# 4_cpu.net
KiCad netlist of a schematic drawn in Altium Designer
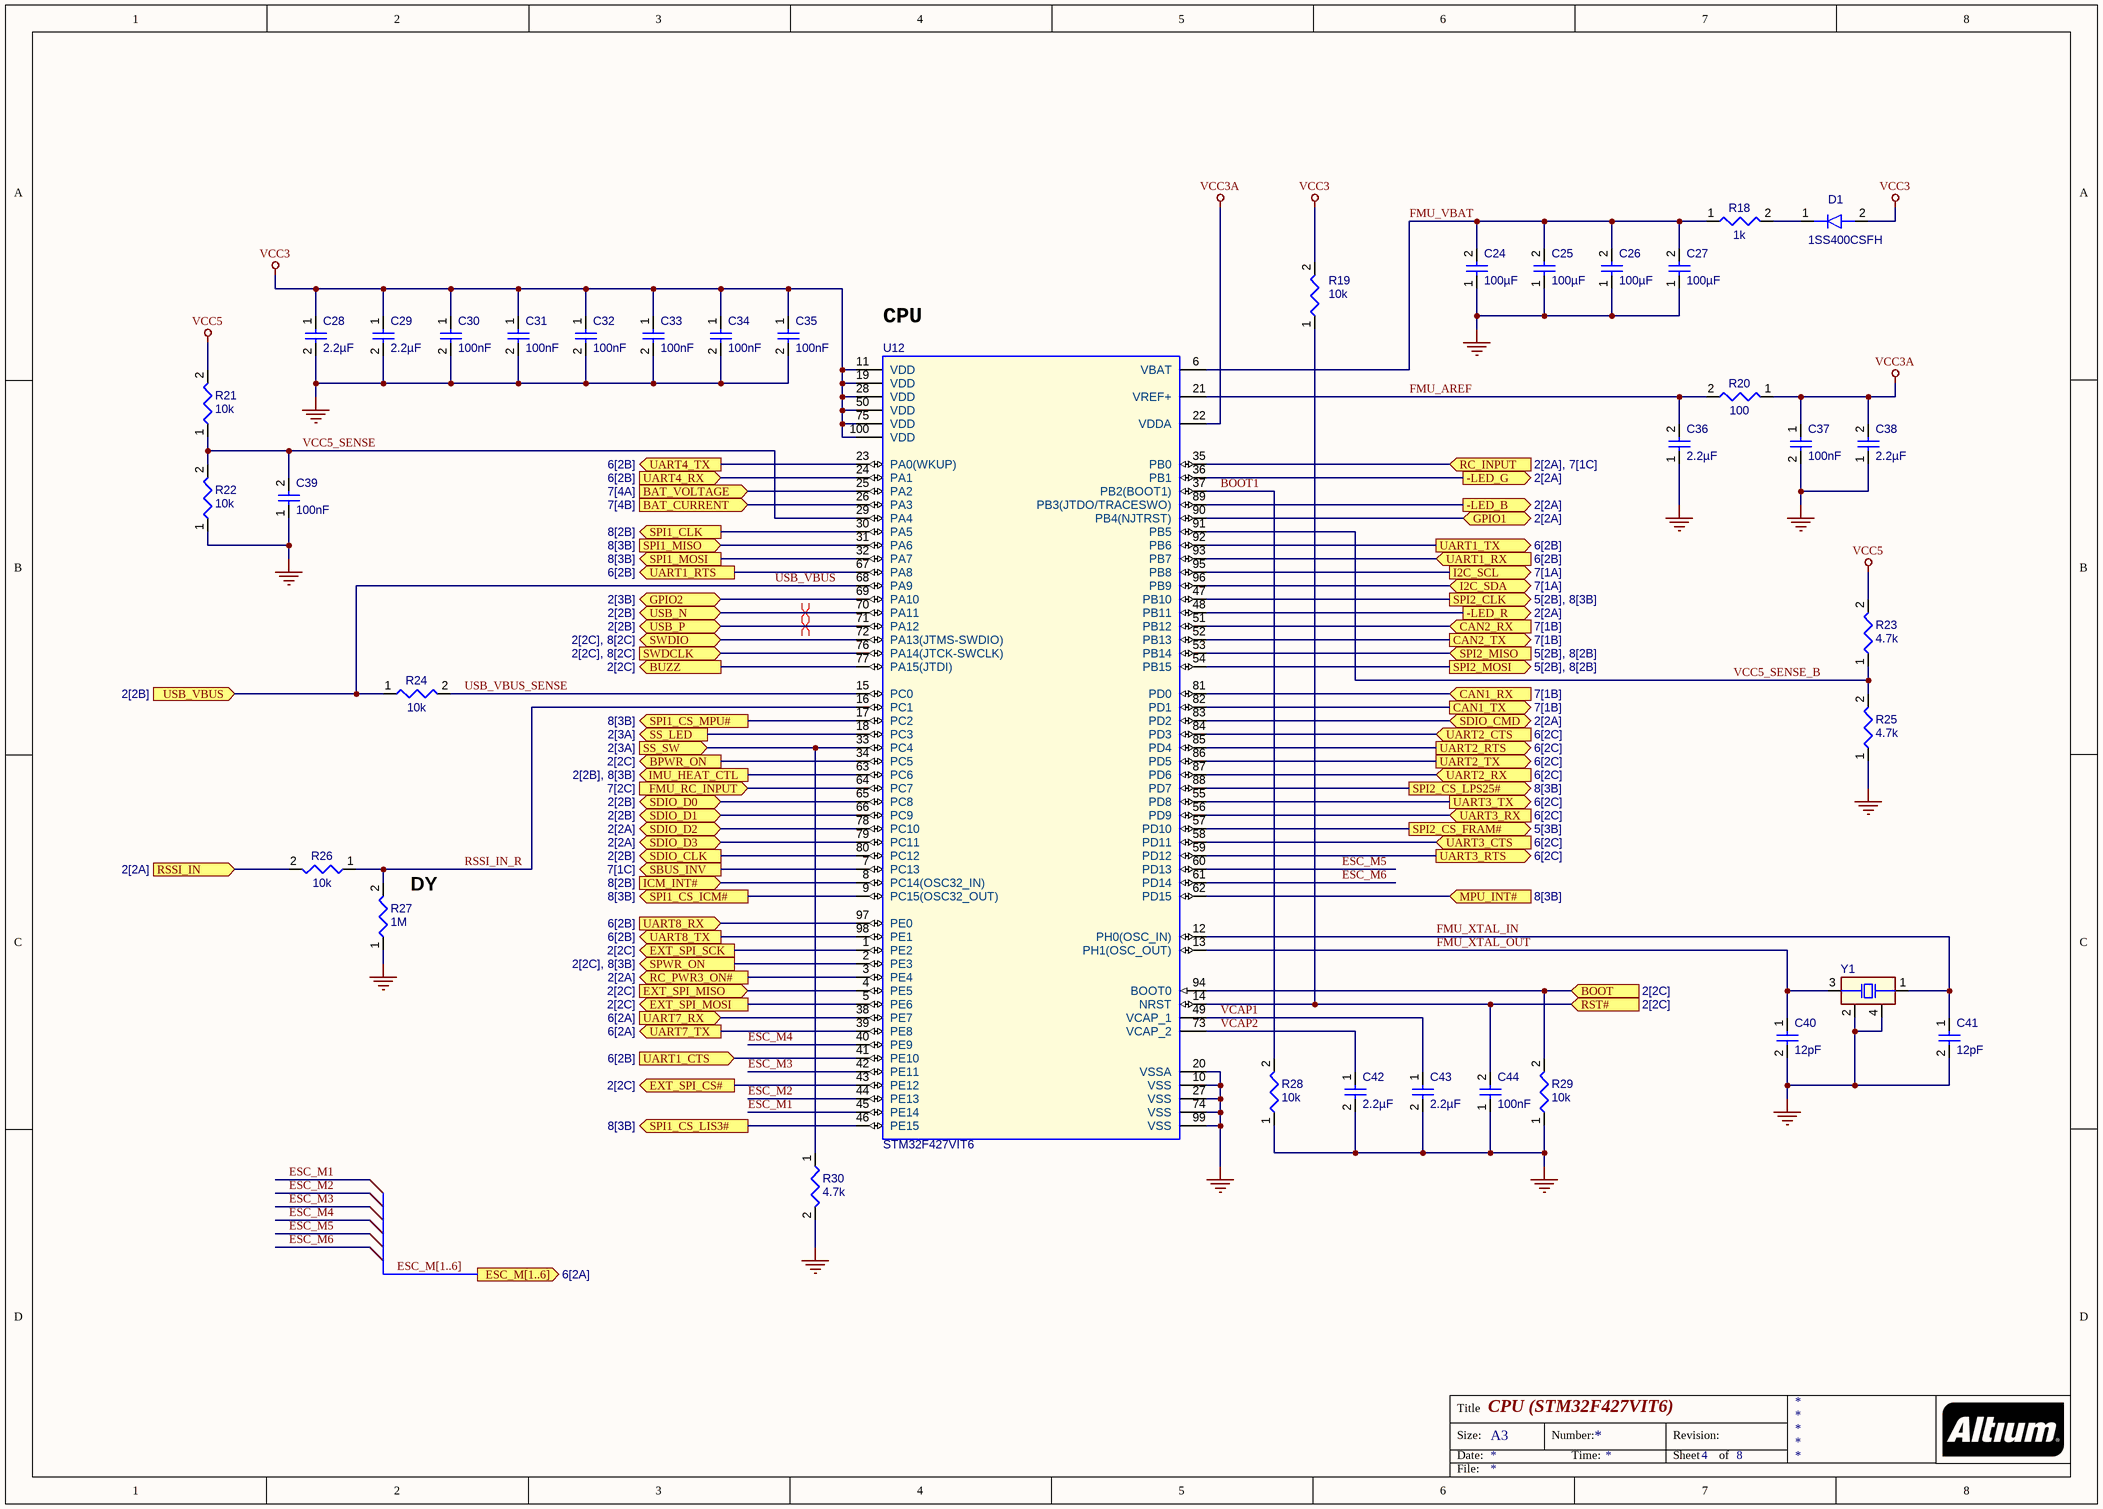
[diagram p0: 4_cpu.SchDoc]

(export (version "E")
  (design (tool "Eeschema 10.0.6"))
  (components
    (comp (ref "C24")
      (value "100µF")
      (footprint "CAPC0805(2012)145_L")
      (description "Chip Capacitor, 100µF +/-20%, 6.3V, 0805, Thickness 1.45 mm")
      (fields (field (name "TOLERANCE") "10%") (field (name "Comment") "Capacitor 100µF +/-20% 6.3V 0805"))
      (libsource (lib "<Company> Server") (part "CAP-NP-2"))
    )
    (comp (ref "C25")
      (value "100µF")
      (footprint "CAPC0805(2012)145_L")
      (description "Chip Capacitor, 100µF +/-20%, 6.3V, 0805, Thickness 1.45 mm")
      (fields (field (name "TOLERANCE") "10%") (field (name "Comment") "Capacitor 100µF +/-20% 6.3V 0805"))
      (libsource (lib "<Company> Server") (part "CAP-NP-2"))
    )
    (comp (ref "C26")
      (value "100µF")
      (footprint "CAPC0805(2012)145_L")
      (description "Chip Capacitor, 100µF +/-20%, 6.3V, 0805, Thickness 1.45 mm")
      (fields (field (name "TOLERANCE") "10%") (field (name "Comment") "Capacitor 100µF +/-20% 6.3V 0805"))
      (libsource (lib "<Company> Server") (part "CAP-NP-2"))
    )
    (comp (ref "C27")
      (value "100µF")
      (footprint "CAPC0805(2012)145_L")
      (description "Chip Capacitor, 100µF +/-20%, 6.3V, 0805, Thickness 1.45 mm")
      (fields (field (name "TOLERANCE") "10%") (field (name "Comment") "Capacitor 100µF +/-20% 6.3V 0805"))
      (libsource (lib "<Company> Server") (part "CAP-NP-2"))
    )
    (comp (ref "C28")
      (value "2.2µF")
      (footprint "CAPC0402(1005)60_L")
      (description "Chip Capacitor, 2,2µF +/-20%, 10V, 0402, Thickness 0.6 mm")
      (fields (field (name "TOLERANCE") "10%") (field (name "Comment") "Capacitor 2,2µF +/-20% 10V 0402"))
      (libsource (lib "<Company> Server") (part "CAP-NP-2"))
    )
    (comp (ref "C29")
      (value "2.2µF")
      (footprint "CAPC0402(1005)60_L")
      (description "Chip Capacitor, 2,2µF +/-20%, 10V, 0402, Thickness 0.6 mm")
      (fields (field (name "TOLERANCE") "10%") (field (name "Comment") "Capacitor 2,2µF +/-20% 10V 0402"))
      (libsource (lib "<Company> Server") (part "CAP-NP-2"))
    )
    (comp (ref "C30")
      (value "100nF")
      (footprint "CAPC0402(1005)60_L")
      (description "Chip Capacitor, 100nF +/-20%, 10V, 0402, Thickness 0.6 mm")
      (fields (field (name "TOLERANCE") "20%") (field (name "Comment") "Capacitor 100nF +/-20% 10V 0402"))
      (libsource (lib "<Company> Server") (part "CAP-NP-2"))
    )
    (comp (ref "C31")
      (value "100nF")
      (footprint "CAPC0402(1005)60_L")
      (description "Chip Capacitor, 100nF +/-20%, 10V, 0402, Thickness 0.6 mm")
      (fields (field (name "TOLERANCE") "20%") (field (name "Comment") "Capacitor 100nF +/-20% 10V 0402"))
      (libsource (lib "<Company> Server") (part "CAP-NP-2"))
    )
    (comp (ref "C32")
      (value "100nF")
      (footprint "CAPC0402(1005)60_L")
      (description "Chip Capacitor, 100nF +/-20%, 10V, 0402, Thickness 0.6 mm")
      (fields (field (name "TOLERANCE") "20%") (field (name "Comment") "Capacitor 100nF +/-20% 10V 0402"))
      (libsource (lib "<Company> Server") (part "CAP-NP-2"))
    )
    (comp (ref "C33")
      (value "100nF")
      (footprint "CAPC0402(1005)60_L")
      (description "Chip Capacitor, 100nF +/-20%, 10V, 0402, Thickness 0.6 mm")
      (fields (field (name "TOLERANCE") "20%") (field (name "Comment") "Capacitor 100nF +/-20% 10V 0402"))
      (libsource (lib "<Company> Server") (part "CAP-NP-2"))
    )
    (comp (ref "C34")
      (value "100nF")
      (footprint "CAPC0402(1005)60_L")
      (description "Chip Capacitor, 100nF +/-20%, 10V, 0402, Thickness 0.6 mm")
      (fields (field (name "TOLERANCE") "20%") (field (name "Comment") "Capacitor 100nF +/-20% 10V 0402"))
      (libsource (lib "<Company> Server") (part "CAP-NP-2"))
    )
    (comp (ref "C35")
      (value "100nF")
      (footprint "CAPC0402(1005)60_L")
      (description "Chip Capacitor, 100nF +/-20%, 10V, 0402, Thickness 0.6 mm")
      (fields (field (name "TOLERANCE") "20%") (field (name "Comment") "Capacitor 100nF +/-20% 10V 0402"))
      (libsource (lib "<Company> Server") (part "CAP-NP-2"))
    )
    (comp (ref "C36")
      (value "2.2µF")
      (footprint "CAPC0402(1005)60_L")
      (description "Chip Capacitor, 2,2µF +/-20%, 10V, 0402, Thickness 0.6 mm")
      (fields (field (name "TOLERANCE") "10%") (field (name "Comment") "Capacitor 2,2µF +/-20% 10V 0402"))
      (libsource (lib "<Company> Server") (part "CAP-NP-2"))
    )
    (comp (ref "C37")
      (value "100nF")
      (footprint "CAPC0402(1005)60_L")
      (description "Chip Capacitor, 100nF +/-20%, 10V, 0402, Thickness 0.6 mm")
      (fields (field (name "TOLERANCE") "20%") (field (name "Comment") "Capacitor 100nF +/-20% 10V 0402"))
      (libsource (lib "<Company> Server") (part "CAP-NP-2"))
    )
    (comp (ref "C38")
      (value "2.2µF")
      (footprint "CAPC0402(1005)60_L")
      (description "Chip Capacitor, 2,2µF +/-20%, 10V, 0402, Thickness 0.6 mm")
      (fields (field (name "TOLERANCE") "10%") (field (name "Comment") "Capacitor 2,2µF +/-20% 10V 0402"))
      (libsource (lib "<Company> Server") (part "CAP-NP-2"))
    )
    (comp (ref "C39")
      (value "100nF")
      (footprint "CAPC0402(1005)60_L")
      (description "Chip Capacitor, 100nF +/-20%, 10V, 0402, Thickness 0.6 mm")
      (fields (field (name "TOLERANCE") "20%") (field (name "Comment") "Capacitor 100nF +/-20% 10V 0402"))
      (libsource (lib "<Company> Server") (part "CAP-NP-2"))
    )
    (comp (ref "C40")
      (value "12pF")
      (footprint "CAPC0402(1005)33_L")
      (description "Chip Capacitor, 12pF +/-10%, 50V, 0402, Thickness 0.33 mm")
      (fields (field (name "TOLERANCE") "20%") (field (name "Comment") "Capacitor 12pF +/-10% 50V 0402"))
      (libsource (lib "<Company> Server") (part "CAP-NP-2"))
    )
    (comp (ref "C41")
      (value "12pF")
      (footprint "CAPC0402(1005)33_L")
      (description "Chip Capacitor, 12pF +/-10%, 50V, 0402, Thickness 0.33 mm")
      (fields (field (name "TOLERANCE") "20%") (field (name "Comment") "Capacitor 12pF +/-10% 50V 0402"))
      (libsource (lib "<Company> Server") (part "CAP-NP-2"))
    )
    (comp (ref "C42")
      (value "2.2µF")
      (footprint "CAPC0402(1005)60_L")
      (description "Chip Capacitor, 2,2µF +/-20%, 10V, 0402, Thickness 0.6 mm")
      (fields (field (name "TOLERANCE") "10%") (field (name "Comment") "Capacitor 2,2µF +/-20% 10V 0402"))
      (libsource (lib "<Company> Server") (part "CAP-NP-2"))
    )
    (comp (ref "C43")
      (value "2.2µF")
      (footprint "CAPC0402(1005)60_L")
      (description "Chip Capacitor, 2,2µF +/-20%, 10V, 0402, Thickness 0.6 mm")
      (fields (field (name "TOLERANCE") "10%") (field (name "Comment") "Capacitor 2,2µF +/-20% 10V 0402"))
      (libsource (lib "<Company> Server") (part "CAP-NP-2"))
    )
    (comp (ref "C44")
      (value "100nF")
      (footprint "CAPC0402(1005)60_L")
      (description "Chip Capacitor, 100nF +/-20%, 10V, 0402, Thickness 0.6 mm")
      (fields (field (name "TOLERANCE") "20%") (field (name "Comment") "Capacitor 100nF +/-20% 10V 0402"))
      (libsource (lib "<Company> Server") (part "CAP-NP-2"))
    )
    (comp (ref "D1")
      (value "1SS400CSFH")
      (footprint "ROHM-VMN2-2_V")
      (description "Switching Diode (High Speed Switching), 80 V, 100 mA, 2-Pin SOD-923, RoHS, Tape and Reel")
      (libsource (lib "<Company> Server") (part "D-KA-2"))
    )
    (comp (ref "R18")
      (value "1k")
      (footprint "RESC0402(1005)_L")
      (description "Chip Resistor, 1 kOhms, +/-5 %, 63 mW, -55 to 155 degC, 0402")
      (fields (field (name "TOLERANCE") "5%") (field (name "POWER") "63mW"))
      (libsource (lib "<Company> Server") (part "RES-2"))
    )
    (comp (ref "R19")
      (value "10k")
      (footprint "RESC0402(1005)_L")
      (description "Chip Resistor, 10 kOhms, +/-1 %, 63 mW, -55 to 125 degC, 0402")
      (fields (field (name "TOLERANCE") "1%") (field (name "POWER") "63mW"))
      (libsource (lib "<Company> Server") (part "RES-2"))
    )
    (comp (ref "R20")
      (value "100")
      (footprint "RESC0402(1005)_L")
      (description "Chip Resistor, 100 Ohms, +/-1 %, 63 mW, -55 to 155 degC, 0402")
      (fields (field (name "TOLERANCE") "1%") (field (name "POWER") "63mW"))
      (libsource (lib "<Company> Server") (part "RES-2"))
    )
    (comp (ref "R21")
      (value "10k")
      (footprint "RESC0402(1005)_L")
      (description "Chip Resistor, 10 kOhms, +/-1 %, 63 mW, -55 to 125 degC, 0402")
      (fields (field (name "TOLERANCE") "1%") (field (name "POWER") "63mW"))
      (libsource (lib "<Company> Server") (part "RES-2"))
    )
    (comp (ref "R22")
      (value "10k")
      (footprint "RESC0402(1005)_L")
      (description "Chip Resistor, 10 kOhms, +/-1 %, 63 mW, -55 to 125 degC, 0402")
      (fields (field (name "TOLERANCE") "1%") (field (name "POWER") "63mW"))
      (libsource (lib "<Company> Server") (part "RES-2"))
    )
    (comp (ref "R23")
      (value "4.7k")
      (footprint "RESC0402(1005)_L")
      (description "Chip Resistor, 4,7 kOhms, +/-1 %, 63 mW, -55 to 155 degC, 0402")
      (fields (field (name "TOLERANCE") "1%") (field (name "POWER") "63mW"))
      (libsource (lib "<Company> Server") (part "RES-2"))
    )
    (comp (ref "R24")
      (value "10k")
      (footprint "RESC0402(1005)_L")
      (description "Chip Resistor, 10 kOhms, +/-1 %, 63 mW, -55 to 125 degC, 0402")
      (fields (field (name "TOLERANCE") "1%") (field (name "POWER") "63mW"))
      (libsource (lib "<Company> Server") (part "RES-2"))
    )
    (comp (ref "R25")
      (value "4.7k")
      (footprint "RESC0402(1005)_L")
      (description "Chip Resistor, 4,7 kOhms, +/-1 %, 63 mW, -55 to 155 degC, 0402")
      (fields (field (name "TOLERANCE") "1%") (field (name "POWER") "63mW"))
      (libsource (lib "<Company> Server") (part "RES-2"))
    )
    (comp (ref "R26")
      (value "10k")
      (footprint "RESC0402(1005)_L")
      (description "Chip Resistor, 10 kOhms, +/-1 %, 63 mW, -55 to 125 degC, 0402")
      (fields (field (name "TOLERANCE") "1%") (field (name "POWER") "63mW"))
      (libsource (lib "<Company> Server") (part "RES-2"))
    )
    (comp (ref "R27")
      (value "1M")
      (footprint "RESC0402(1005)_L")
      (description "Chip Resistor, 1 MOhms, +/-5 %, 63 mW, -55 to 155 degC, 0402")
      (fields (field (name "TOLERANCE") "5%") (field (name "POWER") "63mW"))
      (libsource (lib "<Company> Server") (part "RES-2"))
    )
    (comp (ref "R28")
      (value "10k")
      (footprint "RESC0402(1005)_L")
      (description "Chip Resistor, 10 kOhms, +/-1 %, 63 mW, -55 to 125 degC, 0402")
      (fields (field (name "TOLERANCE") "1%") (field (name "POWER") "63mW"))
      (libsource (lib "<Company> Server") (part "RES-2"))
    )
    (comp (ref "R29")
      (value "10k")
      (footprint "RESC0402(1005)_L")
      (description "Chip Resistor, 10 kOhms, +/-1 %, 63 mW, -55 to 125 degC, 0402")
      (fields (field (name "TOLERANCE") "1%") (field (name "POWER") "63mW"))
      (libsource (lib "<Company> Server") (part "RES-2"))
    )
    (comp (ref "R30")
      (value "4.7k")
      (footprint "RESC0402(1005)_L")
      (description "Chip Resistor, 4,7 kOhms, +/-1 %, 63 mW, -55 to 155 degC, 0402")
      (fields (field (name "TOLERANCE") "1%") (field (name "POWER") "63mW"))
      (libsource (lib "<Company> Server") (part "RES-2"))
    )
    (comp (ref "U12")
      (value "STM32F427VIT6")
      (footprint "STM-LQFP100")
      (libsource (lib "<Company> Server") (part "CMP-00125-5"))
    )
    (comp (ref "Y1")
      (value "FA-12824.0000MF10Z-W3")
      (footprint "EPSON-FA-128_V")
      (description "Crystal, 24 MHz, +/- 10 ppm, -20 to 75 degC, 4-Pin SMD, RoHS, Tape and Reel")
      (libsource (lib "<Company> Server") (part "CMP-00014-7"))
    )
  )
  (nets
    (net (code "1") (name "/-LED_B") (class "Default")
      (node (ref "U12") (pin "89") (pinfunction "PB3(JTDO/TRACESWO)_89") (pintype "bidirectional"))
    )
    (net (code "2") (name "/-LED_G") (class "Default")
      (node (ref "U12") (pin "36") (pinfunction "PB1_36") (pintype "bidirectional"))
    )
    (net (code "3") (name "/-LED_R") (class "Default")
      (node (ref "U12") (pin "48") (pinfunction "PB11_48") (pintype "bidirectional"))
    )
    (net (code "4") (name "/BAT_CURRENT") (class "Default")
      (node (ref "U12") (pin "26") (pinfunction "PA3_26") (pintype "bidirectional"))
    )
    (net (code "5") (name "/BAT_VOLTAGE") (class "Default")
      (node (ref "U12") (pin "25") (pinfunction "PA2_25") (pintype "bidirectional"))
    )
    (net (code "6") (name "/BOOT") (class "Default")
      (node (ref "R29") (pin "2") (pinfunction "2_2") (pintype "passive"))
      (node (ref "U12") (pin "94") (pinfunction "BOOT0_94") (pintype "input"))
    )
    (net (code "7") (name "/BOOT1") (class "Default")
      (node (ref "R28") (pin "2") (pinfunction "2_2") (pintype "passive"))
      (node (ref "U12") (pin "37") (pinfunction "PB2(BOOT1)_37") (pintype "bidirectional"))
    )
    (net (code "8") (name "/BPWR_ON") (class "Default")
      (node (ref "U12") (pin "34") (pinfunction "PC5_34") (pintype "bidirectional"))
    )
    (net (code "9") (name "/BUZZ") (class "Default")
      (node (ref "U12") (pin "77") (pinfunction "PA15(JTDI)_77") (pintype "bidirectional"))
    )
    (net (code "10") (name "/CAN1_RX") (class "Default")
      (node (ref "U12") (pin "81") (pinfunction "PD0_81") (pintype "bidirectional"))
    )
    (net (code "11") (name "/CAN1_TX") (class "Default")
      (node (ref "U12") (pin "82") (pinfunction "PD1_82") (pintype "bidirectional"))
    )
    (net (code "12") (name "/CAN2_RX") (class "Default")
      (node (ref "U12") (pin "51") (pinfunction "PB12_51") (pintype "bidirectional"))
    )
    (net (code "13") (name "/CAN2_TX") (class "Default")
      (node (ref "U12") (pin "52") (pinfunction "PB13_52") (pintype "bidirectional"))
    )
    (net (code "14") (name "/ESC_M1") (class "Default")
      (node (ref "U12") (pin "45") (pinfunction "PE14_45") (pintype "bidirectional"))
    )
    (net (code "15") (name "/ESC_M2") (class "Default")
      (node (ref "U12") (pin "44") (pinfunction "PE13_44") (pintype "bidirectional"))
    )
    (net (code "16") (name "/ESC_M3") (class "Default")
      (node (ref "U12") (pin "42") (pinfunction "PE11_42") (pintype "bidirectional"))
    )
    (net (code "17") (name "/ESC_M4") (class "Default")
      (node (ref "U12") (pin "40") (pinfunction "PE9_40") (pintype "bidirectional"))
    )
    (net (code "18") (name "/ESC_M5") (class "Default")
      (node (ref "U12") (pin "60") (pinfunction "PD13_60") (pintype "bidirectional"))
    )
    (net (code "19") (name "/ESC_M6") (class "Default")
      (node (ref "U12") (pin "61") (pinfunction "PD14_61") (pintype "bidirectional"))
    )
    (net (code "21") (name "/EXT_SPI_CS#") (class "Default")
      (node (ref "U12") (pin "43") (pinfunction "PE12_43") (pintype "bidirectional"))
    )
    (net (code "22") (name "/EXT_SPI_MISO") (class "Default")
      (node (ref "U12") (pin "4") (pinfunction "PE5_4") (pintype "bidirectional"))
    )
    (net (code "23") (name "/EXT_SPI_MOSI") (class "Default")
      (node (ref "U12") (pin "5") (pinfunction "PE6_5") (pintype "bidirectional"))
    )
    (net (code "24") (name "/EXT_SPI_SCK") (class "Default")
      (node (ref "U12") (pin "1") (pinfunction "PE2_1") (pintype "bidirectional"))
    )
    (net (code "25") (name "/FMU_AREF") (class "Default")
      (node (ref "C36") (pin "2") (pinfunction "2_2") (pintype "passive"))
      (node (ref "R20") (pin "2") (pinfunction "2_2") (pintype "passive"))
      (node (ref "U12") (pin "21") (pinfunction "VREF+_21") (pintype "power_in"))
    )
    (net (code "26") (name "/FMU_RC_INPUT") (class "Default")
      (node (ref "U12") (pin "64") (pinfunction "PC7_64") (pintype "bidirectional"))
    )
    (net (code "27") (name "/FMU_VBAT") (class "Default")
      (node (ref "C24") (pin "2") (pinfunction "2_2") (pintype "passive"))
      (node (ref "C25") (pin "2") (pinfunction "2_2") (pintype "passive"))
      (node (ref "C26") (pin "2") (pinfunction "2_2") (pintype "passive"))
      (node (ref "C27") (pin "2") (pinfunction "2_2") (pintype "passive"))
      (node (ref "R18") (pin "1") (pinfunction "1_1") (pintype "passive"))
      (node (ref "U12") (pin "6") (pinfunction "VBAT_6") (pintype "power_in"))
    )
    (net (code "28") (name "/FMU_XTAL_IN") (class "Default")
      (node (ref "C41") (pin "1") (pinfunction "1_1") (pintype "passive"))
      (node (ref "U12") (pin "12") (pinfunction "PH0(OSC_IN)_12") (pintype "bidirectional"))
      (node (ref "Y1") (pin "1") (pinfunction "X1_1") (pintype "passive"))
    )
    (net (code "29") (name "/FMU_XTAL_OUT") (class "Default")
      (node (ref "C40") (pin "1") (pinfunction "1_1") (pintype "passive"))
      (node (ref "U12") (pin "13") (pinfunction "PH1(OSC_OUT)_13") (pintype "bidirectional"))
      (node (ref "Y1") (pin "3") (pinfunction "X2_3") (pintype "passive"))
    )
    (net (code "30") (name "/GPIO1") (class "Default")
      (node (ref "U12") (pin "90") (pinfunction "PB4(NJTRST)_90") (pintype "bidirectional"))
    )
    (net (code "31") (name "/GPIO2") (class "Default")
      (node (ref "U12") (pin "69") (pinfunction "PA10_69") (pintype "bidirectional"))
    )
    (net (code "32") (name "/I2C_SCL") (class "Default")
      (node (ref "U12") (pin "95") (pinfunction "PB8_95") (pintype "bidirectional"))
    )
    (net (code "33") (name "/I2C_SDA") (class "Default")
      (node (ref "U12") (pin "96") (pinfunction "PB9_96") (pintype "bidirectional"))
    )
    (net (code "34") (name "/ICM_INT#") (class "Default")
      (node (ref "U12") (pin "8") (pinfunction "PC14(OSC32_IN)_8") (pintype "bidirectional"))
    )
    (net (code "35") (name "/IMU_HEAT_CTL") (class "Default")
      (node (ref "U12") (pin "63") (pinfunction "PC6_63") (pintype "bidirectional"))
    )
    (net (code "36") (name "/MPU_INT#") (class "Default")
      (node (ref "U12") (pin "62") (pinfunction "PD15_62") (pintype "bidirectional"))
    )
    (net (code "37") (name "/RC_INPUT") (class "Default")
      (node (ref "U12") (pin "35") (pinfunction "PB0_35") (pintype "bidirectional"))
    )
    (net (code "38") (name "/RC_PWR3_ON#") (class "Default")
      (node (ref "U12") (pin "3") (pinfunction "PE4_3") (pintype "bidirectional"))
    )
    (net (code "39") (name "/RSSI_IN") (class "Default")
      (node (ref "R26") (pin "2") (pinfunction "2_2") (pintype "passive"))
    )
    (net (code "40") (name "/RSSI_IN_R") (class "Default")
      (node (ref "R26") (pin "1") (pinfunction "1_1") (pintype "passive"))
      (node (ref "R27") (pin "2") (pinfunction "2_2") (pintype "passive"))
      (node (ref "U12") (pin "16") (pinfunction "PC1_16") (pintype "bidirectional"))
    )
    (net (code "41") (name "/RST#") (class "Default")
      (node (ref "C44") (pin "2") (pinfunction "2_2") (pintype "passive"))
      (node (ref "R19") (pin "1") (pinfunction "1_1") (pintype "passive"))
      (node (ref "U12") (pin "14") (pinfunction "NRST_14") (pintype "bidirectional"))
    )
    (net (code "42") (name "/SBUS_INV") (class "Default")
      (node (ref "U12") (pin "7") (pinfunction "PC13_7") (pintype "bidirectional"))
    )
    (net (code "43") (name "/SDIO_CLK") (class "Default")
      (node (ref "U12") (pin "80") (pinfunction "PC12_80") (pintype "bidirectional"))
    )
    (net (code "44") (name "/SDIO_CMD") (class "Default")
      (node (ref "U12") (pin "83") (pinfunction "PD2_83") (pintype "bidirectional"))
    )
    (net (code "45") (name "/SDIO_D0") (class "Default")
      (node (ref "U12") (pin "65") (pinfunction "PC8_65") (pintype "bidirectional"))
    )
    (net (code "46") (name "/SDIO_D1") (class "Default")
      (node (ref "U12") (pin "66") (pinfunction "PC9_66") (pintype "bidirectional"))
    )
    (net (code "47") (name "/SDIO_D2") (class "Default")
      (node (ref "U12") (pin "78") (pinfunction "PC10_78") (pintype "bidirectional"))
    )
    (net (code "48") (name "/SDIO_D3") (class "Default")
      (node (ref "U12") (pin "79") (pinfunction "PC11_79") (pintype "bidirectional"))
    )
    (net (code "49") (name "/SPI1_CLK") (class "Default")
      (node (ref "U12") (pin "30") (pinfunction "PA5_30") (pintype "bidirectional"))
    )
    (net (code "50") (name "/SPI1_CS_ICM#") (class "Default")
      (node (ref "U12") (pin "9") (pinfunction "PC15(OSC32_OUT)_9") (pintype "bidirectional"))
    )
    (net (code "51") (name "/SPI1_CS_LIS3#") (class "Default")
      (node (ref "U12") (pin "46") (pinfunction "PE15_46") (pintype "bidirectional"))
    )
    (net (code "52") (name "/SPI1_CS_MPU#") (class "Default")
      (node (ref "U12") (pin "17") (pinfunction "PC2_17") (pintype "bidirectional"))
    )
    (net (code "53") (name "/SPI1_MISO") (class "Default")
      (node (ref "U12") (pin "31") (pinfunction "PA6_31") (pintype "bidirectional"))
    )
    (net (code "54") (name "/SPI1_MOSI") (class "Default")
      (node (ref "U12") (pin "32") (pinfunction "PA7_32") (pintype "bidirectional"))
    )
    (net (code "55") (name "/SPI2_CLK") (class "Default")
      (node (ref "U12") (pin "47") (pinfunction "PB10_47") (pintype "bidirectional"))
    )
    (net (code "56") (name "/SPI2_CS_FRAM#") (class "Default")
      (node (ref "U12") (pin "57") (pinfunction "PD10_57") (pintype "bidirectional"))
    )
    (net (code "57") (name "/SPI2_CS_LPS25#") (class "Default")
      (node (ref "U12") (pin "88") (pinfunction "PD7_88") (pintype "bidirectional"))
    )
    (net (code "58") (name "/SPI2_MISO") (class "Default")
      (node (ref "U12") (pin "53") (pinfunction "PB14_53") (pintype "bidirectional"))
    )
    (net (code "59") (name "/SPI2_MOSI") (class "Default")
      (node (ref "U12") (pin "54") (pinfunction "PB15_54") (pintype "bidirectional"))
    )
    (net (code "60") (name "/SPWR_ON") (class "Default")
      (node (ref "U12") (pin "2") (pinfunction "PE3_2") (pintype "bidirectional"))
    )
    (net (code "61") (name "/SS_LED") (class "Default")
      (node (ref "U12") (pin "18") (pinfunction "PC3_18") (pintype "bidirectional"))
    )
    (net (code "62") (name "/SS_SW") (class "Default")
      (node (ref "R30") (pin "1") (pinfunction "1_1") (pintype "passive"))
      (node (ref "U12") (pin "33") (pinfunction "PC4_33") (pintype "bidirectional"))
    )
    (net (code "63") (name "/SWDCLK") (class "Default")
      (node (ref "U12") (pin "76") (pinfunction "PA14(JTCK-SWCLK)_76") (pintype "bidirectional"))
    )
    (net (code "64") (name "/SWDIO") (class "Default")
      (node (ref "U12") (pin "72") (pinfunction "PA13(JTMS-SWDIO)_72") (pintype "bidirectional"))
    )
    (net (code "65") (name "/UART1_CTS") (class "Default")
      (node (ref "U12") (pin "41") (pinfunction "PE10_41") (pintype "bidirectional"))
    )
    (net (code "66") (name "/UART1_RTS") (class "Default")
      (node (ref "U12") (pin "67") (pinfunction "PA8_67") (pintype "bidirectional"))
    )
    (net (code "67") (name "/UART1_RX") (class "Default")
      (node (ref "U12") (pin "93") (pinfunction "PB7_93") (pintype "bidirectional"))
    )
    (net (code "68") (name "/UART1_TX") (class "Default")
      (node (ref "U12") (pin "92") (pinfunction "PB6_92") (pintype "bidirectional"))
    )
    (net (code "69") (name "/UART2_CTS") (class "Default")
      (node (ref "U12") (pin "84") (pinfunction "PD3_84") (pintype "bidirectional"))
    )
    (net (code "70") (name "/UART2_RTS") (class "Default")
      (node (ref "U12") (pin "85") (pinfunction "PD4_85") (pintype "bidirectional"))
    )
    (net (code "71") (name "/UART2_RX") (class "Default")
      (node (ref "U12") (pin "87") (pinfunction "PD6_87") (pintype "bidirectional"))
    )
    (net (code "72") (name "/UART2_TX") (class "Default")
      (node (ref "U12") (pin "86") (pinfunction "PD5_86") (pintype "bidirectional"))
    )
    (net (code "73") (name "/UART3_CTS") (class "Default")
      (node (ref "U12") (pin "58") (pinfunction "PD11_58") (pintype "bidirectional"))
    )
    (net (code "74") (name "/UART3_RTS") (class "Default")
      (node (ref "U12") (pin "59") (pinfunction "PD12_59") (pintype "bidirectional"))
    )
    (net (code "75") (name "/UART3_RX") (class "Default")
      (node (ref "U12") (pin "56") (pinfunction "PD9_56") (pintype "bidirectional"))
    )
    (net (code "76") (name "/UART3_TX") (class "Default")
      (node (ref "U12") (pin "55") (pinfunction "PD8_55") (pintype "bidirectional"))
    )
    (net (code "77") (name "/UART4_RX") (class "Default")
      (node (ref "U12") (pin "24") (pinfunction "PA1_24") (pintype "bidirectional"))
    )
    (net (code "78") (name "/UART4_TX") (class "Default")
      (node (ref "U12") (pin "23") (pinfunction "PA0(WKUP)_23") (pintype "bidirectional"))
    )
    (net (code "79") (name "/UART7_RX") (class "Default")
      (node (ref "U12") (pin "38") (pinfunction "PE7_38") (pintype "bidirectional"))
    )
    (net (code "80") (name "/UART7_TX") (class "Default")
      (node (ref "U12") (pin "39") (pinfunction "PE8_39") (pintype "bidirectional"))
    )
    (net (code "81") (name "/UART8_RX") (class "Default")
      (node (ref "U12") (pin "97") (pinfunction "PE0_97") (pintype "bidirectional"))
    )
    (net (code "82") (name "/UART8_TX") (class "Default")
      (node (ref "U12") (pin "98") (pinfunction "PE1_98") (pintype "bidirectional"))
    )
    (net (code "83") (name "/USB_N") (class "Default")
      (node (ref "U12") (pin "70") (pinfunction "PA11_70") (pintype "bidirectional"))
    )
    (net (code "84") (name "/USB_P") (class "Default")
      (node (ref "U12") (pin "71") (pinfunction "PA12_71") (pintype "bidirectional"))
    )
    (net (code "85") (name "/USB_VBUS") (class "Default")
      (node (ref "R24") (pin "1") (pinfunction "1_1") (pintype "passive"))
      (node (ref "U12") (pin "68") (pinfunction "PA9_68") (pintype "bidirectional"))
    )
    (net (code "86") (name "/USB_VBUS_SENSE") (class "Default")
      (node (ref "R24") (pin "2") (pinfunction "2_2") (pintype "passive"))
      (node (ref "U12") (pin "15") (pinfunction "PC0_15") (pintype "bidirectional"))
    )
    (net (code "87") (name "/VCAP1") (class "Default")
      (node (ref "C43") (pin "1") (pinfunction "1_1") (pintype "passive"))
      (node (ref "U12") (pin "49") (pinfunction "VCAP_1_49") (pintype "passive"))
    )
    (net (code "88") (name "/VCAP2") (class "Default")
      (node (ref "C42") (pin "1") (pinfunction "1_1") (pintype "passive"))
      (node (ref "U12") (pin "73") (pinfunction "VCAP_2_73") (pintype "passive"))
    )
    (net (code "89") (name "/VCC5_SENSE") (class "Default")
      (node (ref "C39") (pin "2") (pinfunction "2_2") (pintype "passive"))
      (node (ref "R21") (pin "1") (pinfunction "1_1") (pintype "passive"))
      (node (ref "R22") (pin "2") (pinfunction "2_2") (pintype "passive"))
      (node (ref "U12") (pin "29") (pinfunction "PA4_29") (pintype "bidirectional"))
    )
    (net (code "90") (name "/VCC5_SENSE_B") (class "Default")
      (node (ref "R23") (pin "1") (pinfunction "1_1") (pintype "passive"))
      (node (ref "R25") (pin "2") (pinfunction "2_2") (pintype "passive"))
      (node (ref "U12") (pin "91") (pinfunction "PB5_91") (pintype "bidirectional"))
    )
    (net (code "91") (name "GND") (class "Default")
      (node (ref "C24") (pin "1") (pinfunction "1_1") (pintype "passive"))
      (node (ref "C25") (pin "1") (pinfunction "1_1") (pintype "passive"))
      (node (ref "C26") (pin "1") (pinfunction "1_1") (pintype "passive"))
      (node (ref "C27") (pin "1") (pinfunction "1_1") (pintype "passive"))
      (node (ref "C28") (pin "2") (pinfunction "2_2") (pintype "passive"))
      (node (ref "C29") (pin "2") (pinfunction "2_2") (pintype "passive"))
      (node (ref "C30") (pin "2") (pinfunction "2_2") (pintype "passive"))
      (node (ref "C31") (pin "2") (pinfunction "2_2") (pintype "passive"))
      (node (ref "C32") (pin "2") (pinfunction "2_2") (pintype "passive"))
      (node (ref "C33") (pin "2") (pinfunction "2_2") (pintype "passive"))
      (node (ref "C34") (pin "2") (pinfunction "2_2") (pintype "passive"))
      (node (ref "C35") (pin "2") (pinfunction "2_2") (pintype "passive"))
      (node (ref "C36") (pin "1") (pinfunction "1_1") (pintype "passive"))
      (node (ref "C37") (pin "2") (pinfunction "2_2") (pintype "passive"))
      (node (ref "C38") (pin "1") (pinfunction "1_1") (pintype "passive"))
      (node (ref "C39") (pin "1") (pinfunction "1_1") (pintype "passive"))
      (node (ref "C40") (pin "2") (pinfunction "2_2") (pintype "passive"))
      (node (ref "C41") (pin "2") (pinfunction "2_2") (pintype "passive"))
      (node (ref "C42") (pin "2") (pinfunction "2_2") (pintype "passive"))
      (node (ref "C43") (pin "2") (pinfunction "2_2") (pintype "passive"))
      (node (ref "C44") (pin "1") (pinfunction "1_1") (pintype "passive"))
      (node (ref "R22") (pin "1") (pinfunction "1_1") (pintype "passive"))
      (node (ref "R25") (pin "1") (pinfunction "1_1") (pintype "passive"))
      (node (ref "R27") (pin "1") (pinfunction "1_1") (pintype "passive"))
      (node (ref "R28") (pin "1") (pinfunction "1_1") (pintype "passive"))
      (node (ref "R29") (pin "1") (pinfunction "1_1") (pintype "passive"))
      (node (ref "R30") (pin "2") (pinfunction "2_2") (pintype "passive"))
      (node (ref "U12") (pin "10") (pinfunction "VSS_10") (pintype "power_in"))
      (node (ref "U12") (pin "20") (pinfunction "VSSA_20") (pintype "power_in"))
      (node (ref "U12") (pin "27") (pinfunction "VSS_27") (pintype "power_in"))
      (node (ref "U12") (pin "74") (pinfunction "VSS_74") (pintype "power_in"))
      (node (ref "U12") (pin "99") (pinfunction "VSS_99") (pintype "power_in"))
      (node (ref "Y1") (pin "2") (pinfunction "NC_2") (pintype "power_in"))
      (node (ref "Y1") (pin "4") (pinfunction "NC_4") (pintype "power_in"))
    )
    (net (code "92") (name "Net-(D1-K)") (class "Default")
      (node (ref "D1") (pin "1") (pinfunction "K_1") (pintype "passive"))
      (node (ref "R18") (pin "2") (pinfunction "2_2") (pintype "passive"))
    )
    (net (code "93") (name "VCC3") (class "Default")
      (node (ref "C28") (pin "1") (pinfunction "1_1") (pintype "passive"))
      (node (ref "C29") (pin "1") (pinfunction "1_1") (pintype "passive"))
      (node (ref "C30") (pin "1") (pinfunction "1_1") (pintype "passive"))
      (node (ref "C31") (pin "1") (pinfunction "1_1") (pintype "passive"))
      (node (ref "C32") (pin "1") (pinfunction "1_1") (pintype "passive"))
      (node (ref "C33") (pin "1") (pinfunction "1_1") (pintype "passive"))
      (node (ref "C34") (pin "1") (pinfunction "1_1") (pintype "passive"))
      (node (ref "C35") (pin "1") (pinfunction "1_1") (pintype "passive"))
      (node (ref "D1") (pin "2") (pinfunction "A_2") (pintype "passive"))
      (node (ref "R19") (pin "2") (pinfunction "2_2") (pintype "passive"))
      (node (ref "U12") (pin "100") (pinfunction "VDD_100") (pintype "power_in"))
      (node (ref "U12") (pin "11") (pinfunction "VDD_11") (pintype "power_in"))
      (node (ref "U12") (pin "19") (pinfunction "VDD_19") (pintype "power_in"))
      (node (ref "U12") (pin "28") (pinfunction "VDD_28") (pintype "power_in"))
      (node (ref "U12") (pin "50") (pinfunction "VDD_50") (pintype "power_in"))
      (node (ref "U12") (pin "75") (pinfunction "VDD_75") (pintype "power_in"))
    )
    (net (code "94") (name "VCC3A") (class "Default")
      (node (ref "C37") (pin "1") (pinfunction "1_1") (pintype "passive"))
      (node (ref "C38") (pin "2") (pinfunction "2_2") (pintype "passive"))
      (node (ref "R20") (pin "1") (pinfunction "1_1") (pintype "passive"))
      (node (ref "U12") (pin "22") (pinfunction "VDDA_22") (pintype "power_in"))
    )
    (net (code "95") (name "VCC5") (class "Default")
      (node (ref "R21") (pin "2") (pinfunction "2_2") (pintype "passive"))
      (node (ref "R23") (pin "2") (pinfunction "2_2") (pintype "passive"))
    )
  )
)
